# inktime_schematic.net
KiCad netlist of a schematic drawn in EAGLE
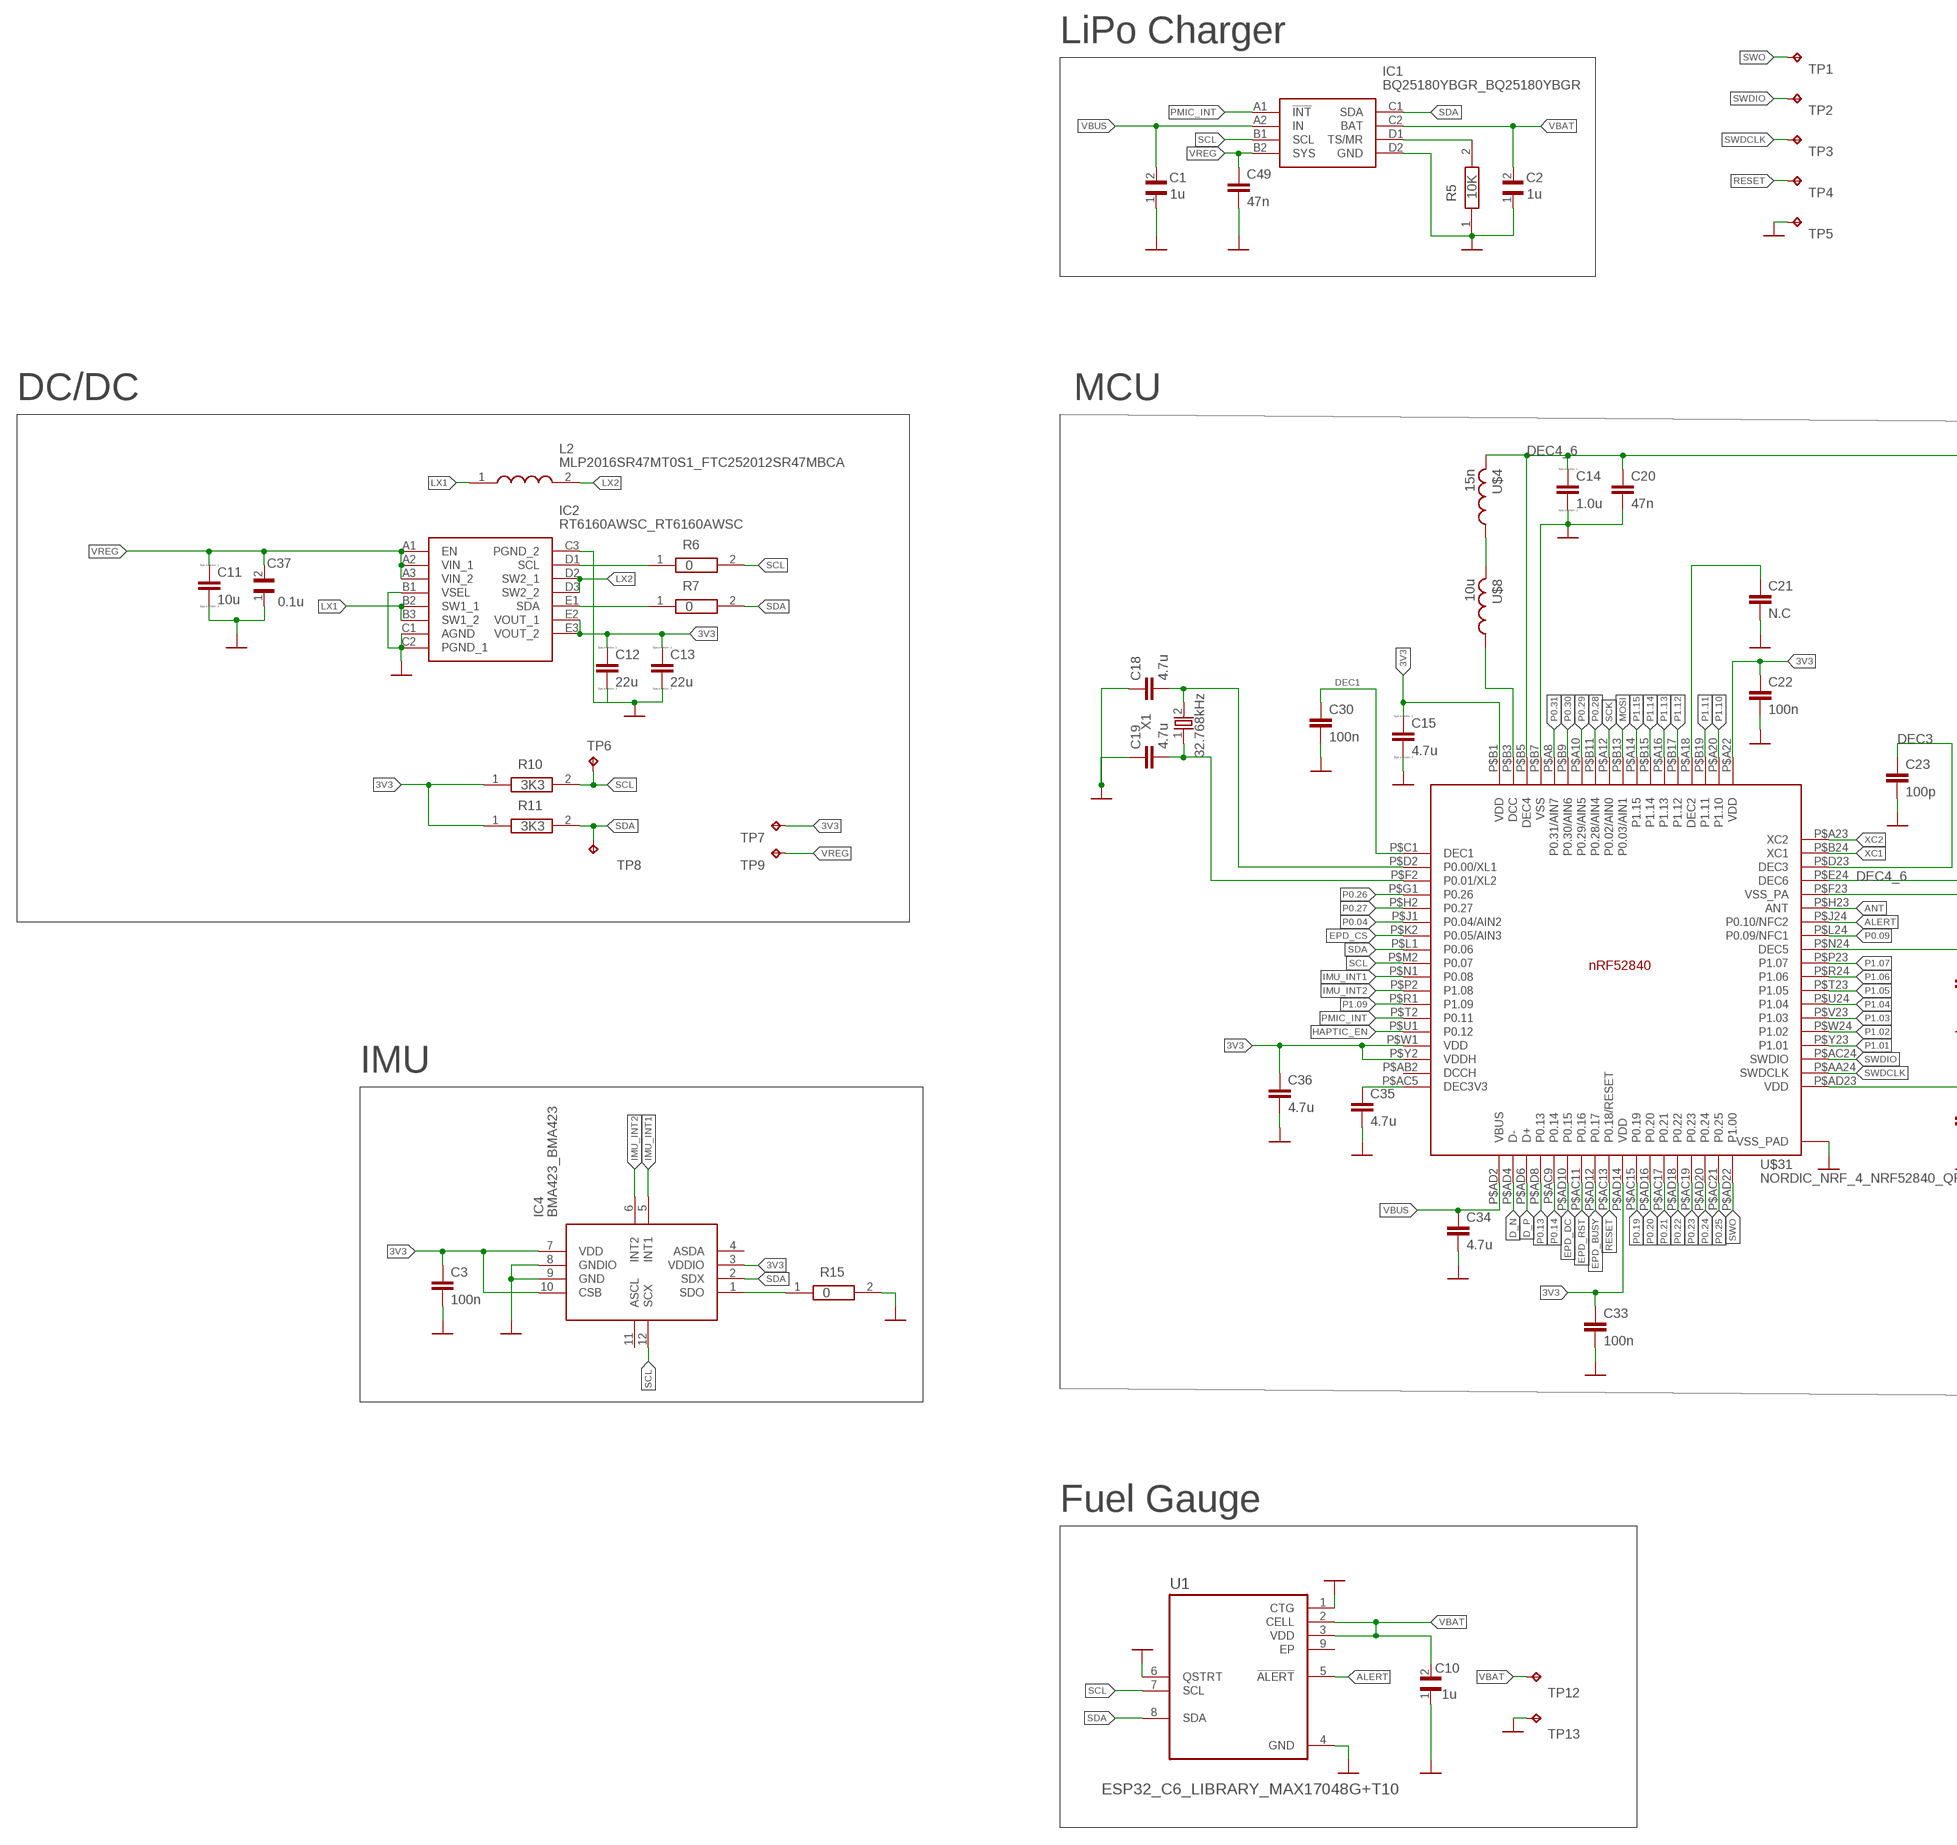
[diagram p0: schematic, sheet 1, part 1 of 2]
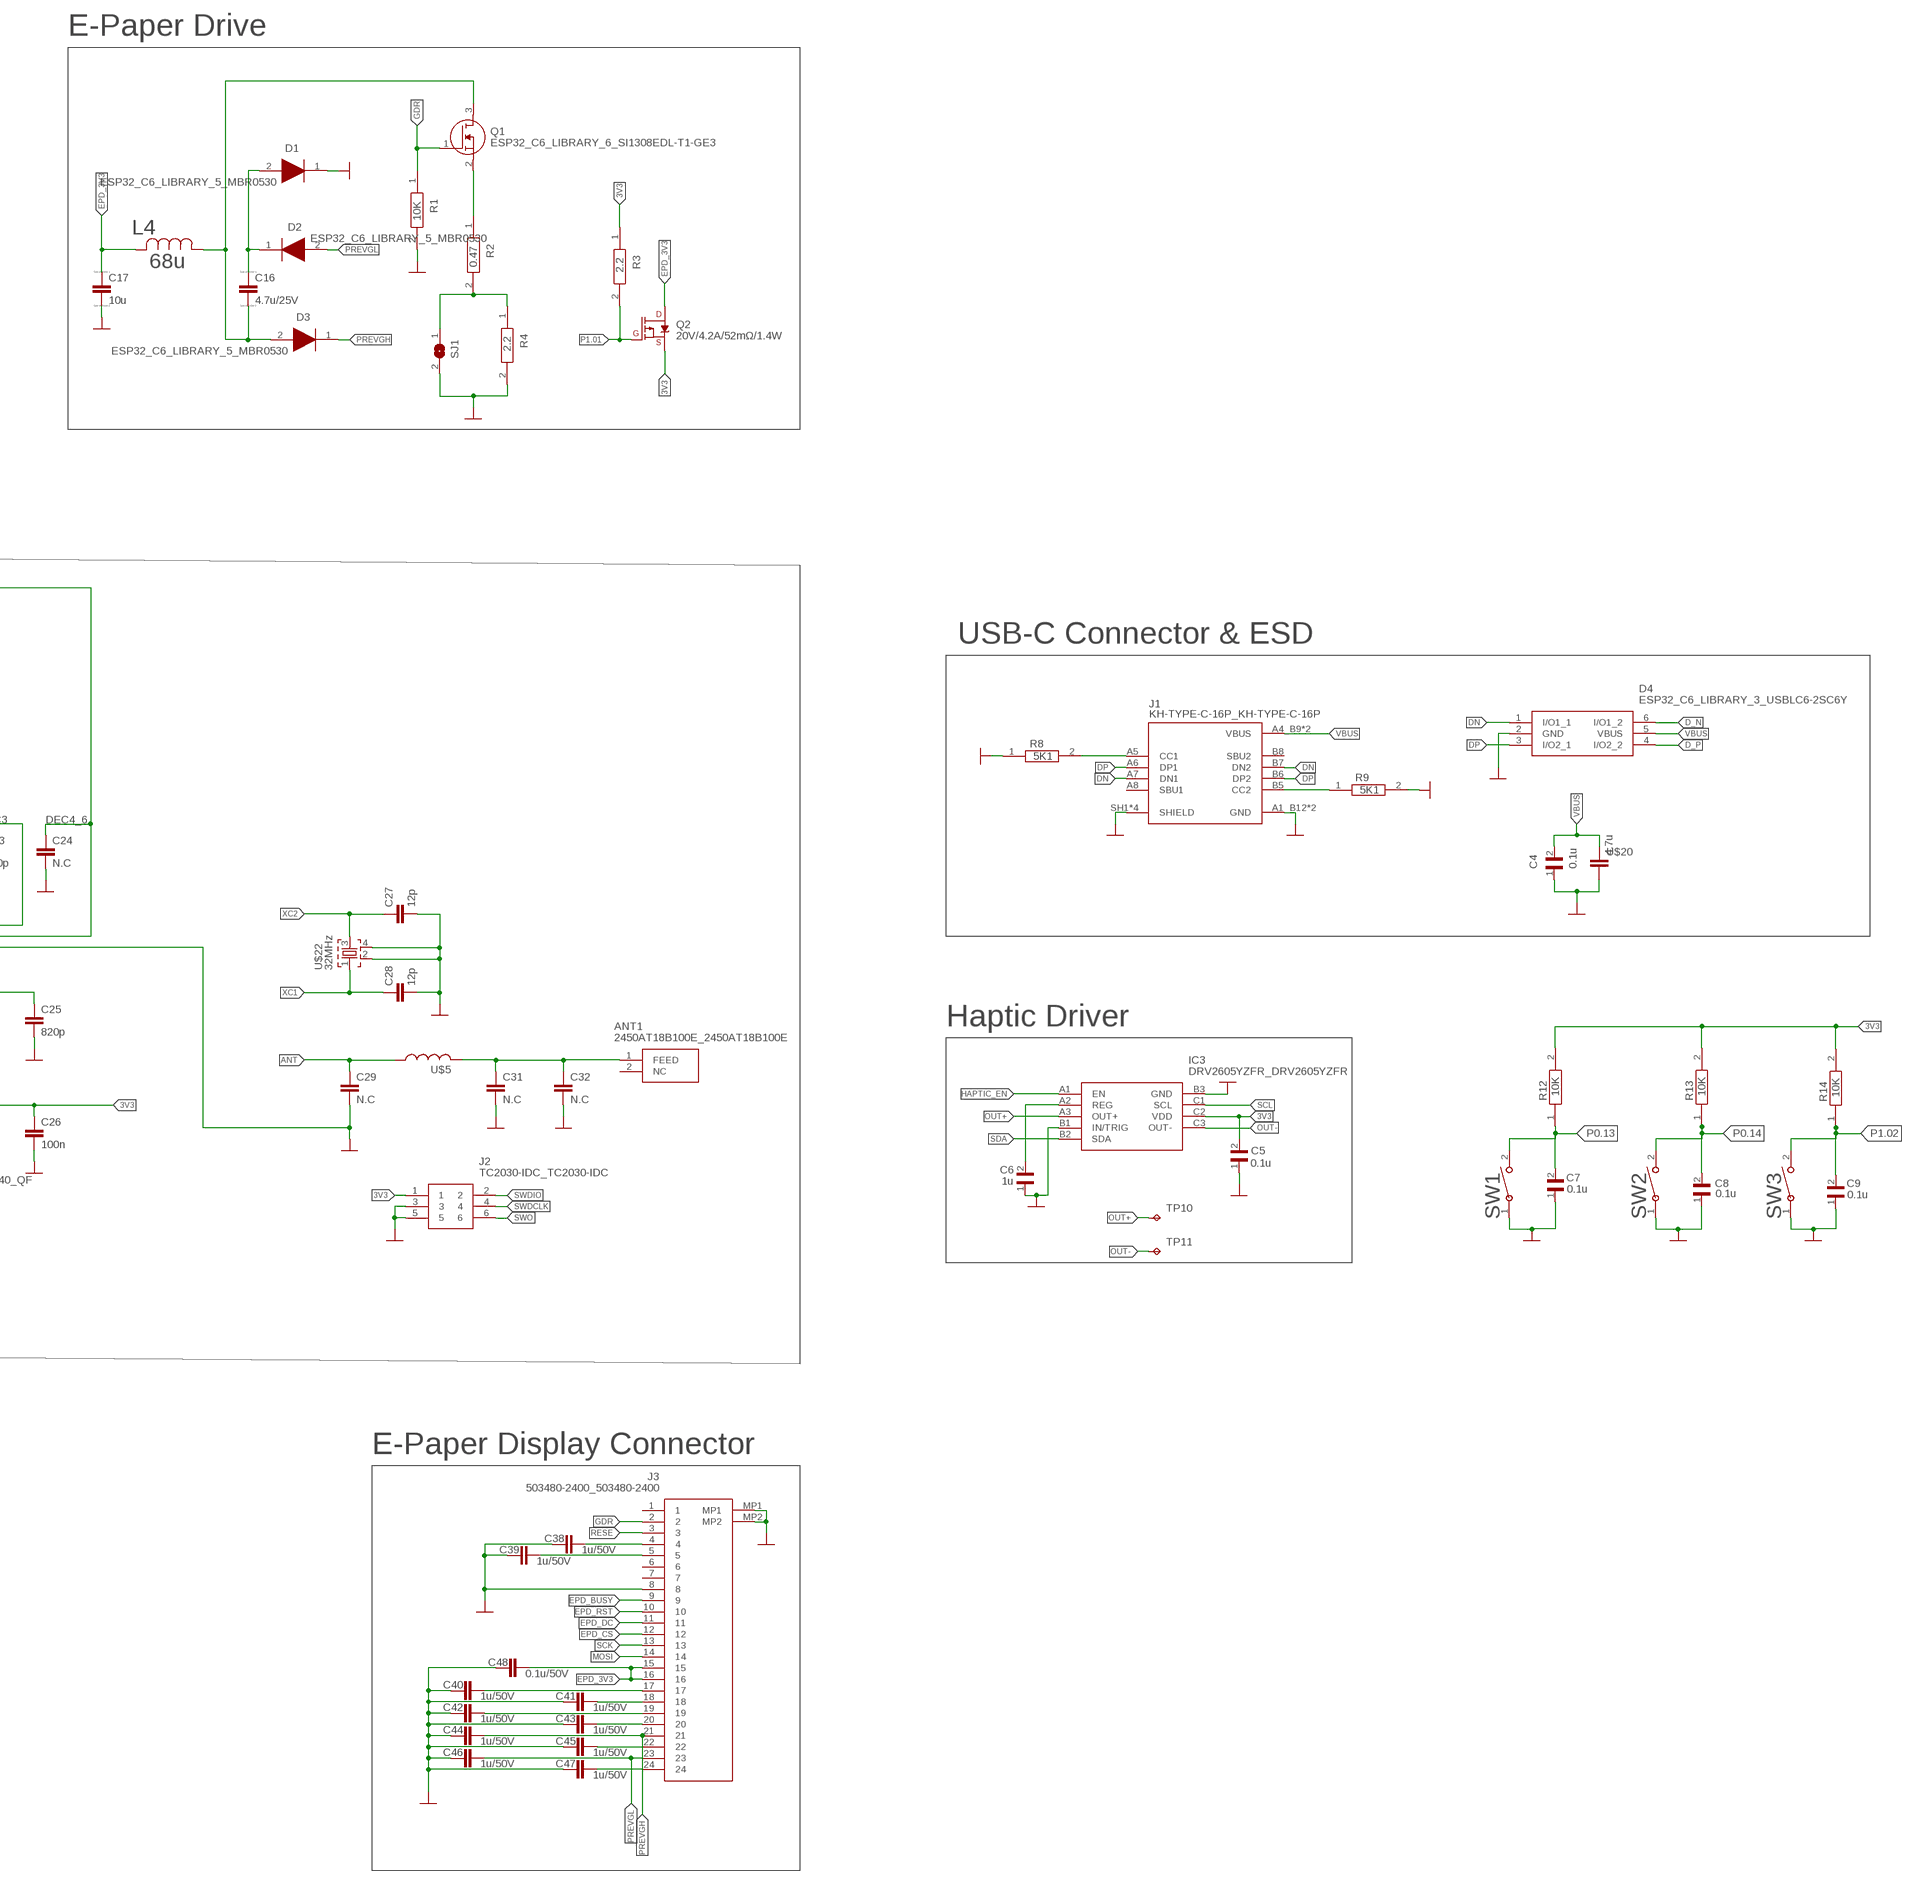
[diagram p1: schematic, sheet 1, part 2 of 2]

(export (version "E")
  (design (tool "Eeschema 10.0.6"))
  (components
    (comp (ref "ANT1")
      (value "2450AT18B100E_2450AT18B100E")
      (footprint "eagle-import:2450AT18B100E_ANTC3216X140N")
      (fields
        (field (name "ARROW_PART_NUMBER") "2450AT18B100E")
        (field (name "MOUSER_PART_NUMBER") "609-2450AT18B100E")
      )
      (libsource (lib "eagle-import") (part "2450AT18B100E_2450AT18B100E"))
    )
    (comp (ref "C1")
      (value "1u")
      (footprint "eagle-import:GRM011R60J152KE01L_2_CAPC0201X13N")
      (fields (field (name "MF") "Murata") (field (name "MP") "GRM011R60J152KE01L"))
      (libsource (lib "eagle-import") (part "GRM011R60J152KE01L_2_GRM011R60J152KE01L"))
    )
    (comp (ref "C2")
      (value "1u")
      (footprint "eagle-import:GRM011R60J152KE01L_2_CAPC0201X13N")
      (fields (field (name "MF") "Murata") (field (name "MP") "GRM011R60J152KE01L"))
      (libsource (lib "eagle-import") (part "GRM011R60J152KE01L_2_GRM011R60J152KE01L"))
    )
    (comp (ref "C3")
      (value "100n")
      (footprint "eagle-import:NORDIC_NRF_3_RESC0201_L")
      (libsource (lib "eagle-import") (part "NORDIC_NRF_3_CAPACITOR_0201_L"))
    )
    (comp (ref "C4")
      (value "0.1u")
      (footprint "eagle-import:GRM011R60J152KE01L_2_CAPC0201X13N")
      (fields (field (name "MF") "Murata") (field (name "MP") "GRM011R60J152KE01L"))
      (libsource (lib "eagle-import") (part "GRM011R60J152KE01L_2_GRM011R60J152KE01L"))
    )
    (comp (ref "C5")
      (value "0.1u")
      (footprint "eagle-import:GRM011R60J152KE01L_2_CAPC0201X13N")
      (fields (field (name "MF") "Murata") (field (name "MP") "GRM011R60J152KE01L"))
      (libsource (lib "eagle-import") (part "GRM011R60J152KE01L_2_GRM011R60J152KE01L"))
    )
    (comp (ref "C6")
      (value "1u")
      (footprint "eagle-import:GRM011R60J152KE01L_2_CAPC0201X13N")
      (fields (field (name "MF") "Murata") (field (name "MP") "GRM011R60J152KE01L"))
      (libsource (lib "eagle-import") (part "GRM011R60J152KE01L_2_GRM011R60J152KE01L"))
    )
    (comp (ref "C7")
      (value "0.1u")
      (footprint "eagle-import:GRM011R60J152KE01L_2_CAPC0201X13N")
      (fields (field (name "MF") "Murata") (field (name "MP") "GRM011R60J152KE01L"))
      (libsource (lib "eagle-import") (part "GRM011R60J152KE01L_2_GRM011R60J152KE01L"))
    )
    (comp (ref "C8")
      (value "0.1u")
      (footprint "eagle-import:GRM011R60J152KE01L_2_CAPC0201X13N")
      (fields (field (name "MF") "Murata") (field (name "MP") "GRM011R60J152KE01L"))
      (libsource (lib "eagle-import") (part "GRM011R60J152KE01L_2_GRM011R60J152KE01L"))
    )
    (comp (ref "C9")
      (value "0.1u")
      (footprint "eagle-import:GRM011R60J152KE01L_2_CAPC0201X13N")
      (fields (field (name "MF") "Murata") (field (name "MP") "GRM011R60J152KE01L"))
      (libsource (lib "eagle-import") (part "GRM011R60J152KE01L_2_GRM011R60J152KE01L"))
    )
    (comp (ref "C10")
      (value "1u")
      (footprint "eagle-import:GRM011R60J152KE01L_2_CAPC0201X13N")
      (fields (field (name "MF") "Murata") (field (name "MP") "GRM011R60J152KE01L"))
      (libsource (lib "eagle-import") (part "GRM011R60J152KE01L_2_GRM011R60J152KE01L"))
    )
    (comp (ref "C11")
      (value "10u")
      (footprint "eagle-import:ESP32_C6_LIBRARY_1_ESP32_WROVER_EAGLE-LTSPICE_C0402")
      (libsource (lib "eagle-import") (part "ESP32_C6_LIBRARY_1_ESP32_WROVER_EAGLE-LTSPICE_CC0402"))
    )
    (comp (ref "C12")
      (value "22u")
      (footprint "eagle-import:ESP32_C6_LIBRARY_1_ESP32_WROVER_EAGLE-LTSPICE_C0402")
      (libsource (lib "eagle-import") (part "ESP32_C6_LIBRARY_1_ESP32_WROVER_EAGLE-LTSPICE_CC0402"))
    )
    (comp (ref "C13")
      (value "22u")
      (footprint "eagle-import:ESP32_C6_LIBRARY_1_ESP32_WROVER_EAGLE-LTSPICE_C0402")
      (libsource (lib "eagle-import") (part "ESP32_C6_LIBRARY_1_ESP32_WROVER_EAGLE-LTSPICE_CC0402"))
    )
    (comp (ref "C14")
      (value "1.0u")
      (footprint "eagle-import:ESP32_C6_LIBRARY_1_ESP32_WROVER_EAGLE-LTSPICE_C0402")
      (libsource (lib "eagle-import") (part "ESP32_C6_LIBRARY_1_ESP32_WROVER_EAGLE-LTSPICE_CC0402"))
    )
    (comp (ref "C15")
      (value "4.7u")
      (footprint "eagle-import:ESP32_C6_LIBRARY_1_ESP32_WROVER_EAGLE-LTSPICE_C0402")
      (libsource (lib "eagle-import") (part "ESP32_C6_LIBRARY_1_ESP32_WROVER_EAGLE-LTSPICE_CC0402"))
    )
    (comp (ref "C16")
      (value "4.7u/25V")
      (footprint "eagle-import:ESP32_C6_LIBRARY_1_ESP32_WROVER_EAGLE-LTSPICE_C0402")
      (libsource (lib "eagle-import") (part "ESP32_C6_LIBRARY_1_ESP32_WROVER_EAGLE-LTSPICE_CC0402"))
    )
    (comp (ref "C17")
      (value "10u")
      (footprint "eagle-import:ESP32_C6_LIBRARY_1_ESP32_WROVER_EAGLE-LTSPICE_C0402")
      (libsource (lib "eagle-import") (part "ESP32_C6_LIBRARY_1_ESP32_WROVER_EAGLE-LTSPICE_CC0402"))
    )
    (comp (ref "C18")
      (value "4.7u")
      (footprint "eagle-import:NORDIC_NRF_3_RESC0201_L")
      (libsource (lib "eagle-import") (part "NORDIC_NRF_3_CAPACITOR_0201_L"))
    )
    (comp (ref "C19")
      (value "4.7u")
      (footprint "eagle-import:NORDIC_NRF_3_RESC0201_L")
      (libsource (lib "eagle-import") (part "NORDIC_NRF_3_CAPACITOR_0201_L"))
    )
    (comp (ref "C20")
      (value "47n")
      (footprint "eagle-import:NORDIC_NRF_3_RESC0201_L")
      (libsource (lib "eagle-import") (part "NORDIC_NRF_3_CAPACITOR_0201_L"))
    )
    (comp (ref "C21")
      (value "N.C")
      (footprint "eagle-import:NORDIC_NRF_3_RESC0201_L")
      (libsource (lib "eagle-import") (part "NORDIC_NRF_3_CAPACITOR_0201_L"))
    )
    (comp (ref "C22")
      (value "100n")
      (footprint "eagle-import:NORDIC_NRF_3_RESC0201_L")
      (libsource (lib "eagle-import") (part "NORDIC_NRF_3_CAPACITOR_0201_L"))
    )
    (comp (ref "C23")
      (value "100p")
      (footprint "eagle-import:NORDIC_NRF_3_RESC0201_L")
      (libsource (lib "eagle-import") (part "NORDIC_NRF_3_CAPACITOR_0201_L"))
    )
    (comp (ref "C24")
      (value "N.C")
      (footprint "eagle-import:NORDIC_NRF_3_RESC0201_L")
      (libsource (lib "eagle-import") (part "NORDIC_NRF_3_CAPACITOR_0201_L"))
    )
    (comp (ref "C25")
      (value "820p")
      (footprint "eagle-import:NORDIC_NRF_3_RESC0201_L")
      (libsource (lib "eagle-import") (part "NORDIC_NRF_3_CAPACITOR_0201_L"))
    )
    (comp (ref "C26")
      (value "100n")
      (footprint "eagle-import:NORDIC_NRF_3_RESC0201_L")
      (libsource (lib "eagle-import") (part "NORDIC_NRF_3_CAPACITOR_0201_L"))
    )
    (comp (ref "C27")
      (value "12p")
      (footprint "eagle-import:NORDIC_NRF_3_RESC0201_L")
      (libsource (lib "eagle-import") (part "NORDIC_NRF_3_CAPACITOR_0201_L"))
    )
    (comp (ref "C28")
      (value "12p")
      (footprint "eagle-import:NORDIC_NRF_3_RESC0201_L")
      (libsource (lib "eagle-import") (part "NORDIC_NRF_3_CAPACITOR_0201_L"))
    )
    (comp (ref "C29")
      (value "N.C")
      (footprint "eagle-import:NORDIC_NRF_3_RESC0201_L")
      (libsource (lib "eagle-import") (part "NORDIC_NRF_3_CAPACITOR_0201_L"))
    )
    (comp (ref "C30")
      (value "100n")
      (footprint "eagle-import:NORDIC_NRF_3_RESC0201_L")
      (libsource (lib "eagle-import") (part "NORDIC_NRF_3_CAPACITOR_0201_L"))
    )
    (comp (ref "C31")
      (value "N.C")
      (footprint "eagle-import:NORDIC_NRF_3_RESC0201_L")
      (libsource (lib "eagle-import") (part "NORDIC_NRF_3_CAPACITOR_0201_L"))
    )
    (comp (ref "C32")
      (value "N.C")
      (footprint "eagle-import:NORDIC_NRF_3_RESC0201_L")
      (libsource (lib "eagle-import") (part "NORDIC_NRF_3_CAPACITOR_0201_L"))
    )
    (comp (ref "C33")
      (value "100n")
      (footprint "eagle-import:NORDIC_NRF_3_RESC0201_L")
      (libsource (lib "eagle-import") (part "NORDIC_NRF_3_CAPACITOR_0201_L"))
    )
    (comp (ref "C34")
      (value "4.7u")
      (footprint "eagle-import:NORDIC_NRF_3_RESC0201_L")
      (libsource (lib "eagle-import") (part "NORDIC_NRF_3_CAPACITOR_0201_L"))
    )
    (comp (ref "C35")
      (value "4.7u")
      (footprint "eagle-import:NORDIC_NRF_3_RESC0201_L")
      (libsource (lib "eagle-import") (part "NORDIC_NRF_3_CAPACITOR_0201_L"))
    )
    (comp (ref "C36")
      (value "4.7u")
      (footprint "eagle-import:NORDIC_NRF_3_RESC0201_L")
      (libsource (lib "eagle-import") (part "NORDIC_NRF_3_CAPACITOR_0201_L"))
    )
    (comp (ref "C37")
      (value "0.1u")
      (footprint "eagle-import:GRM011R60J152KE01L_2_CAPC0201X13N")
      (fields (field (name "MF") "Murata") (field (name "MP") "GRM011R60J152KE01L"))
      (libsource (lib "eagle-import") (part "GRM011R60J152KE01L_2_GRM011R60J152KE01L"))
    )
    (comp (ref "C38")
      (value "1u/50V")
      (footprint "eagle-import:NORDIC_NRF_3_RESC0201_L")
      (libsource (lib "eagle-import") (part "NORDIC_NRF_3_CAPACITOR_0201_L"))
    )
    (comp (ref "C39")
      (value "1u/50V")
      (footprint "eagle-import:NORDIC_NRF_3_RESC0201_L")
      (libsource (lib "eagle-import") (part "NORDIC_NRF_3_CAPACITOR_0201_L"))
    )
    (comp (ref "C40")
      (value "1u/50V")
      (footprint "eagle-import:NORDIC_NRF_3_RESC0201_L")
      (libsource (lib "eagle-import") (part "NORDIC_NRF_3_CAPACITOR_0201_L"))
    )
    (comp (ref "C41")
      (value "1u/50V")
      (footprint "eagle-import:NORDIC_NRF_3_RESC0201_L")
      (libsource (lib "eagle-import") (part "NORDIC_NRF_3_CAPACITOR_0201_L"))
    )
    (comp (ref "C42")
      (value "1u/50V")
      (footprint "eagle-import:NORDIC_NRF_3_RESC0201_L")
      (libsource (lib "eagle-import") (part "NORDIC_NRF_3_CAPACITOR_0201_L"))
    )
    (comp (ref "C43")
      (value "1u/50V")
      (footprint "eagle-import:NORDIC_NRF_3_RESC0201_L")
      (libsource (lib "eagle-import") (part "NORDIC_NRF_3_CAPACITOR_0201_L"))
    )
    (comp (ref "C44")
      (value "1u/50V")
      (footprint "eagle-import:NORDIC_NRF_3_RESC0201_L")
      (libsource (lib "eagle-import") (part "NORDIC_NRF_3_CAPACITOR_0201_L"))
    )
    (comp (ref "C45")
      (value "1u/50V")
      (footprint "eagle-import:NORDIC_NRF_3_RESC0201_L")
      (libsource (lib "eagle-import") (part "NORDIC_NRF_3_CAPACITOR_0201_L"))
    )
    (comp (ref "C46")
      (value "1u/50V")
      (footprint "eagle-import:NORDIC_NRF_3_RESC0201_L")
      (libsource (lib "eagle-import") (part "NORDIC_NRF_3_CAPACITOR_0201_L"))
    )
    (comp (ref "C47")
      (value "1u/50V")
      (footprint "eagle-import:NORDIC_NRF_3_RESC0201_L")
      (libsource (lib "eagle-import") (part "NORDIC_NRF_3_CAPACITOR_0201_L"))
    )
    (comp (ref "C48")
      (value "0.1u/50V")
      (footprint "eagle-import:NORDIC_NRF_3_RESC0201_L")
      (libsource (lib "eagle-import") (part "NORDIC_NRF_3_CAPACITOR_0201_L"))
    )
    (comp (ref "C49")
      (value "47n")
      (footprint "eagle-import:NORDIC_NRF_3_RESC0201_L")
      (libsource (lib "eagle-import") (part "NORDIC_NRF_3_CAPACITOR_0201_L"))
    )
    (comp (ref "D1")
      (value "ESP32_C6_LIBRARY_5_MBR0530")
      (footprint "eagle-import:ESP32_C6_LIBRARY_5_SOD3716X135N")
      (fields (field (name "MF") "ON Semiconductor") (field (name "MP") "MBR0530"))
      (libsource (lib "eagle-import") (part "ESP32_C6_LIBRARY_5_MBR0530"))
    )
    (comp (ref "D2")
      (value "ESP32_C6_LIBRARY_5_MBR0530")
      (footprint "eagle-import:ESP32_C6_LIBRARY_5_SOD3716X135N")
      (fields (field (name "MF") "ON Semiconductor") (field (name "MP") "MBR0530"))
      (libsource (lib "eagle-import") (part "ESP32_C6_LIBRARY_5_MBR0530"))
    )
    (comp (ref "D3")
      (value "ESP32_C6_LIBRARY_5_MBR0530")
      (footprint "eagle-import:ESP32_C6_LIBRARY_5_SOD3716X135N")
      (fields (field (name "MF") "ON Semiconductor") (field (name "MP") "MBR0530"))
      (libsource (lib "eagle-import") (part "ESP32_C6_LIBRARY_5_MBR0530"))
    )
    (comp (ref "D4")
      (value "ESP32_C6_LIBRARY_3_USBLC6-2SC6Y")
      (footprint "eagle-import:ESP32_C6_LIBRARY_3_SOT95P280X145-6N")
      (fields (field (name "MF") "STMicroelectronics") (field (name "MP") "USBLC6-2SC6Y"))
      (libsource (lib "eagle-import") (part "ESP32_C6_LIBRARY_3_USBLC6-2SC6Y"))
    )
    (comp (ref "IC1")
      (value "BQ25180YBGR_BQ25180YBGR")
      (footprint "eagle-import:BQ25180YBGR_BGA8C40P2X4_100X155X50")
      (fields
        (field (name "ARROW_PART_NUMBER") "BQ25180YBGR")
        (field (name "MOUSER_PART_NUMBER") "595-BQ25180YBGR")
      )
      (libsource (lib "eagle-import") (part "BQ25180YBGR_BQ25180YBGR"))
    )
    (comp (ref "IC2")
      (value "RT6160AWSC_RT6160AWSC")
      (footprint "eagle-import:RT6160AWSC_BGA15C40P3X5_140X230X60")
      (fields
        (field (name "MANUFACTURER_PART_NUMBER") "RT6160AWSC")
        (field (name "MOUSER_PART_NUMBER") "835-RT6160AWSC")
      )
      (libsource (lib "eagle-import") (part "RT6160AWSC_RT6160AWSC"))
    )
    (comp (ref "IC3")
      (value "DRV2605YZFR_DRV2605YZFR")
      (footprint "eagle-import:DRV2605YZFR_BGA9C50P3X3_144X144X62")
      (fields (field (name "ARROW_PART_NUMBER") "DRV2605YZFR"))
      (libsource (lib "eagle-import") (part "DRV2605YZFR_DRV2605YZFR"))
    )
    (comp (ref "IC4")
      (value "BMA423_BMA423")
      (footprint "eagle-import:BMA423_BMA423")
      (fields (field (name "ARROW_PART_NUMBER") "BMA423") (field (name "MOUSER_PART_NUMBER") "262-BMA423"))
      (libsource (lib "eagle-import") (part "BMA423_BMA423"))
    )
    (comp (ref "J1")
      (value "KH-TYPE-C-16P_KH-TYPE-C-16P")
      (footprint "eagle-import:KH-TYPE-C-16P_KINGHELM_KH-TYPE-C-16P")
      (fields (field (name "MF") "kinghelm") (field (name "MP") "KH-TYPE-C-16P"))
      (libsource (lib "eagle-import") (part "KH-TYPE-C-16P_KH-TYPE-C-16P"))
    )
    (comp (ref "J2")
      (value "TC2030-IDC_TC2030-IDC")
      (footprint "eagle-import:TC2030-IDC_TC2030IDC")
      (fields (field (name "MANUFACTURER_PART_NUMBER") "TC2030-IDC"))
      (libsource (lib "eagle-import") (part "TC2030-IDC_TC2030-IDC"))
    )
    (comp (ref "J3")
      (value "503480-2400_503480-2400")
      (footprint "eagle-import:503480-2400_5034802400")
      (fields
        (field (name "MANUFACTURER_PART_NUMBER") "503480-2400")
        (field (name "MOUSER_PART_NUMBER") "538-503480-2400")
      )
      (libsource (lib "eagle-import") (part "503480-2400_503480-2400"))
    )
    (comp (ref "L2")
      (value "MLP2016SR47MT0S1_FTC252012SR47MBCA")
      (footprint "eagle-import:MLP2016SR47MT0S1_INDC2016X100N")
      (fields (field (name "MANUFACTURER_PART_NUMBER") "FTC252012SR47MBCA"))
      (libsource (lib "eagle-import") (part "MLP2016SR47MT0S1_FTC252012SR47MBCA"))
    )
    (comp (ref "L4")
      (value "68u")
      (footprint "eagle-import:ESP32_C6_LIBRARY_2_IND_4828-WE-TPC_WRE")
      (fields
        (field (name "MANUFACTURER_PART_NUMBER") "744043680")
        (field (name "COPYRIGHT") "Copyright (C) 2024 Ultra Librarian. All rights reserved.")
      )
      (libsource (lib "eagle-import") (part "ESP32_C6_LIBRARY_2_744043680IND_4828-WE-TPC_WRE"))
    )
    (comp (ref "Q1")
      (value "ESP32_C6_LIBRARY_6_SI1308EDL-T1-GE3")
      (footprint "eagle-import:ESP32_C6_LIBRARY_6_SOT65P210X110-3N")
      (fields (field (name "MF") "Vishay Siliconix") (field (name "MP") "SI1308EDL-T1-GE3"))
      (libsource (lib "eagle-import") (part "ESP32_C6_LIBRARY_6_SI1308EDL-T1-GE3"))
    )
    (comp (ref "Q2")
      (value "20V/4.2A/52mΩ/1.4W")
      (footprint "eagle-import:ESP32_C6_LIBRARY_4_ESP32_C6_LIBRARY_4_ESP32_C6_LIBRARY_4_ESP32_C6_LIBRARY_4_ESP32_WROVER_SPARKFUN-DISCRETESEMI_SOT23-3")
      (libsource (lib "eagle-import") (part "ESP32_C6_LIBRARY_4_ESP32_WROVER_SPARKFUN-DISCRETESEMI_MOSFET_PCH-DMG2305UX-7"))
    )
    (comp (ref "R1")
      (value "10K")
      (footprint "eagle-import:ERA-1AEB3401C_0201")
      (libsource (lib "eagle-import") (part "ERA-1AEB3401C_CPF0201D7K68C1"))
    )
    (comp (ref "R2")
      (value "0.47")
      (footprint "eagle-import:ERA-1AEB3401C_0201")
      (libsource (lib "eagle-import") (part "ERA-1AEB3401C_CPF0201D7K68C1"))
    )
    (comp (ref "R3")
      (value "2.2")
      (footprint "eagle-import:ERA-1AEB3401C_0201")
      (libsource (lib "eagle-import") (part "ERA-1AEB3401C_CPF0201D7K68C1"))
    )
    (comp (ref "R4")
      (value "2.2")
      (footprint "eagle-import:ERA-1AEB3401C_0201")
      (libsource (lib "eagle-import") (part "ERA-1AEB3401C_CPF0201D7K68C1"))
    )
    (comp (ref "R5")
      (value "10K")
      (footprint "eagle-import:ERA-1AEB3401C_0201")
      (libsource (lib "eagle-import") (part "ERA-1AEB3401C_CPF0201D7K68C1"))
    )
    (comp (ref "R6")
      (value "0")
      (footprint "eagle-import:ERA-1AEB3401C_0201")
      (libsource (lib "eagle-import") (part "ERA-1AEB3401C_CPF0201D7K68C1"))
    )
    (comp (ref "R7")
      (value "0")
      (footprint "eagle-import:ERA-1AEB3401C_0201")
      (libsource (lib "eagle-import") (part "ERA-1AEB3401C_CPF0201D7K68C1"))
    )
    (comp (ref "R8")
      (value "5K1")
      (footprint "eagle-import:ERA-1AEB3401C_0201")
      (libsource (lib "eagle-import") (part "ERA-1AEB3401C_CPF0201D7K68C1"))
    )
    (comp (ref "R9")
      (value "5K1")
      (footprint "eagle-import:ERA-1AEB3401C_0201")
      (libsource (lib "eagle-import") (part "ERA-1AEB3401C_CPF0201D7K68C1"))
    )
    (comp (ref "R10")
      (value "3K3")
      (footprint "eagle-import:ERA-1AEB3401C_0201")
      (libsource (lib "eagle-import") (part "ERA-1AEB3401C_CPF0201D7K68C1"))
    )
    (comp (ref "R11")
      (value "3K3")
      (footprint "eagle-import:ERA-1AEB3401C_0201")
      (libsource (lib "eagle-import") (part "ERA-1AEB3401C_CPF0201D7K68C1"))
    )
    (comp (ref "R12")
      (value "10K")
      (footprint "eagle-import:ERA-1AEB3401C_0201")
      (libsource (lib "eagle-import") (part "ERA-1AEB3401C_CPF0201D7K68C1"))
    )
    (comp (ref "R13")
      (value "10K")
      (footprint "eagle-import:ERA-1AEB3401C_0201")
      (libsource (lib "eagle-import") (part "ERA-1AEB3401C_CPF0201D7K68C1"))
    )
    (comp (ref "R14")
      (value "10K")
      (footprint "eagle-import:ERA-1AEB3401C_0201")
      (libsource (lib "eagle-import") (part "ERA-1AEB3401C_CPF0201D7K68C1"))
    )
    (comp (ref "R15")
      (value "0")
      (footprint "eagle-import:ERA-1AEB3401C_0201")
      (libsource (lib "eagle-import") (part "ERA-1AEB3401C_CPF0201D7K68C1"))
    )
    (comp (ref "SJ1")
      (value "ESP32_C6_LIBRARY_7_JUMPER_SJ")
      (footprint "eagle-import:ESP32_C6_LIBRARY_7_JUMPER_SJ")
      (libsource (lib "eagle-import") (part "ESP32_C6_LIBRARY_7_JUMPER_SJ"))
    )
    (comp (ref "SW1")
      (value "2025-10-22_07-23-44_LIBRARY_EVP-AKE31ASW_EVP-AKE31A_PAN")
      (footprint "eagle-import:2025-10-22_07-23-44_LIBRARY_SW_EVP-AKE31A_PAN")
      (fields
        (field (name "MANUFACTURER_PART_NUMBER") "EVP-AKE31A")
        (field (name "COPYRIGHT") "Copyright (C) 2025 Ultra Librarian. All rights reserved.")
      )
      (libsource (lib "eagle-import") (part "2025-10-22_07-23-44_LIBRARY_EVP-AKE31ASW_EVP-AKE31A_PAN"))
    )
    (comp (ref "SW2")
      (value "2025-10-22_07-23-44_LIBRARY_EVP-AKE31ASW_EVP-AKE31A_PAN")
      (footprint "eagle-import:2025-10-22_07-23-44_LIBRARY_SW_EVP-AKE31A_PAN")
      (fields
        (field (name "MANUFACTURER_PART_NUMBER") "EVP-AKE31A")
        (field (name "COPYRIGHT") "Copyright (C) 2025 Ultra Librarian. All rights reserved.")
      )
      (libsource (lib "eagle-import") (part "2025-10-22_07-23-44_LIBRARY_EVP-AKE31ASW_EVP-AKE31A_PAN"))
    )
    (comp (ref "SW3")
      (value "2025-10-22_07-23-44_LIBRARY_EVP-AKE31ASW_EVP-AKE31A_PAN")
      (footprint "eagle-import:2025-10-22_07-23-44_LIBRARY_SW_EVP-AKE31A_PAN")
      (fields
        (field (name "MANUFACTURER_PART_NUMBER") "EVP-AKE31A")
        (field (name "COPYRIGHT") "Copyright (C) 2025 Ultra Librarian. All rights reserved.")
      )
      (libsource (lib "eagle-import") (part "2025-10-22_07-23-44_LIBRARY_EVP-AKE31ASW_EVP-AKE31A_PAN"))
    )
    (comp (ref "TP1")
      (value "HECTOR_WATCH_1_TPTP20R")
      (footprint "eagle-import:HECTOR_WATCH_1_TP20R")
      (libsource (lib "eagle-import") (part "HECTOR_WATCH_1_TPTP20R"))
    )
    (comp (ref "TP2")
      (value "HECTOR_WATCH_1_TPTP20R")
      (footprint "eagle-import:HECTOR_WATCH_1_TP20R")
      (libsource (lib "eagle-import") (part "HECTOR_WATCH_1_TPTP20R"))
    )
    (comp (ref "TP3")
      (value "HECTOR_WATCH_1_TPTP20R")
      (footprint "eagle-import:HECTOR_WATCH_1_TP20R")
      (libsource (lib "eagle-import") (part "HECTOR_WATCH_1_TPTP20R"))
    )
    (comp (ref "TP4")
      (value "HECTOR_WATCH_1_TPTP20R")
      (footprint "eagle-import:HECTOR_WATCH_1_TP20R")
      (libsource (lib "eagle-import") (part "HECTOR_WATCH_1_TPTP20R"))
    )
    (comp (ref "TP5")
      (value "HECTOR_WATCH_1_TPTP20R")
      (footprint "eagle-import:HECTOR_WATCH_1_TP20R")
      (libsource (lib "eagle-import") (part "HECTOR_WATCH_1_TPTP20R"))
    )
    (comp (ref "TP6")
      (value "HECTOR_WATCH_1_TPTP20R")
      (footprint "eagle-import:HECTOR_WATCH_1_TP20R")
      (libsource (lib "eagle-import") (part "HECTOR_WATCH_1_TPTP20R"))
    )
    (comp (ref "TP7")
      (value "HECTOR_WATCH_1_TPTP20R")
      (footprint "eagle-import:HECTOR_WATCH_1_TP20R")
      (libsource (lib "eagle-import") (part "HECTOR_WATCH_1_TPTP20R"))
    )
    (comp (ref "TP8")
      (value "HECTOR_WATCH_1_TPTP20R")
      (footprint "eagle-import:HECTOR_WATCH_1_TP20R")
      (libsource (lib "eagle-import") (part "HECTOR_WATCH_1_TPTP20R"))
    )
    (comp (ref "TP9")
      (value "HECTOR_WATCH_1_TPTP20R")
      (footprint "eagle-import:HECTOR_WATCH_1_TP20R")
      (libsource (lib "eagle-import") (part "HECTOR_WATCH_1_TPTP20R"))
    )
    (comp (ref "TP10")
      (value "HECTOR_WATCH_1_TPTP20R")
      (footprint "eagle-import:HECTOR_WATCH_1_TP20R")
      (libsource (lib "eagle-import") (part "HECTOR_WATCH_1_TPTP20R"))
    )
    (comp (ref "TP11")
      (value "HECTOR_WATCH_1_TPTP20R")
      (footprint "eagle-import:HECTOR_WATCH_1_TP20R")
      (libsource (lib "eagle-import") (part "HECTOR_WATCH_1_TPTP20R"))
    )
    (comp (ref "TP12")
      (value "HECTOR_WATCH_1_TPTP20R")
      (footprint "eagle-import:HECTOR_WATCH_1_TP20R")
      (libsource (lib "eagle-import") (part "HECTOR_WATCH_1_TPTP20R"))
    )
    (comp (ref "TP13")
      (value "HECTOR_WATCH_1_TPTP20R")
      (footprint "eagle-import:HECTOR_WATCH_1_TP20R")
      (libsource (lib "eagle-import") (part "HECTOR_WATCH_1_TPTP20R"))
    )
    (comp (ref "U$4")
      (value "15n")
      (footprint "eagle-import:NORDIC_NRF_2_RESC0402_L")
      (libsource (lib "eagle-import") (part "NORDIC_NRF_2_INDUCTOR_0402_L"))
    )
    (comp (ref "U$5")
      (value "NORDIC_NRF_2_INDUCTOR_0402_L")
      (footprint "eagle-import:NORDIC_NRF_2_RESC0402_L")
      (libsource (lib "eagle-import") (part "NORDIC_NRF_2_INDUCTOR_0402_L"))
    )
    (comp (ref "U$8")
      (value "10u")
      (footprint "eagle-import:NORDIC_NRF_2_RESC0402_L")
      (libsource (lib "eagle-import") (part "NORDIC_NRF_2_INDUCTOR_0402_L"))
    )
    (comp (ref "U$20")
      (value "4.7u")
      (footprint "eagle-import:NORDIC_NRF_3_RESC0201_L")
      (libsource (lib "eagle-import") (part "NORDIC_NRF_3_CAPACITOR_0201_L"))
    )
    (comp (ref "U$22")
      (value "32MHz")
      (footprint "eagle-import:NORDIC_NRF_BT-XTAL_2016_N")
      (libsource (lib "eagle-import") (part "NORDIC_NRF_XTAL_32MHZ"))
    )
    (comp (ref "U$31")
      (value "NORDIC_NRF_4_NRF52840_QF")
      (footprint "eagle-import:NORDIC_NRF_4_AQFN50P700X700X85_HS-74N")
      (libsource (lib "eagle-import") (part "NORDIC_NRF_4_NRF52840_QF"))
    )
    (comp (ref "U1")
      (value "ESP32_C6_LIBRARY_MAX17048G+T10")
      (footprint "eagle-import:ESP32_C6_LIBRARY_SON50P200X200X80-9N")
      (fields (field (name "MF") "Analog Devices") (field (name "MP") "MAX17048G+T10"))
      (libsource (lib "eagle-import") (part "ESP32_C6_LIBRARY_MAX17048G+T10"))
    )
    (comp (ref "X1")
      (value "32.768kHz")
      (footprint "eagle-import:NORDIC_NRF_1_XTAL_3215_N")
      (libsource (lib "eagle-import") (part "NORDIC_NRF_1_XTAL_32KHZ"))
    )
  )
  (nets
    (net (code "1") (name "/DEC1") (class "Default")
      (node (ref "C30") (pin "1") (pinfunction "1_1") (pintype "passive"))
      (node (ref "U$31") (pin "P$C1") (pinfunction "DEC1_P$C1") (pintype "power_in"))
    )
    (net (code "2") (name "/DEC3") (class "Default")
      (node (ref "C23") (pin "1") (pinfunction "1_1") (pintype "passive"))
      (node (ref "U$31") (pin "P$D23") (pinfunction "DEC3_P$D23") (pintype "bidirectional"))
    )
    (net (code "3") (name "/DEC4_6") (class "Default")
      (node (ref "C14") (pin "1") (pinfunction "1_1") (pintype "passive"))
      (node (ref "C20") (pin "1") (pinfunction "1_1") (pintype "passive"))
      (node (ref "C24") (pin "1") (pinfunction "1_1") (pintype "passive"))
      (node (ref "U$31") (pin "P$B5") (pinfunction "DEC4_P$B5") (pintype "power_in"))
      (node (ref "U$31") (pin "P$E24") (pinfunction "DEC6_P$E24") (pintype "bidirectional"))
      (node (ref "U$4") (pin "2") (pinfunction "2_2") (pintype "passive"))
    )
    (net (code "4") (name "/EP") (class "Default")
      (node (ref "U1") (pin "9") (pinfunction "EP_9") (pintype "power_in"))
    )
    (net (code "5") (name "3V3") (class "Default")
      (node (ref "C12") (pin "1") (pinfunction "1_1") (pintype "passive"))
      (node (ref "C13") (pin "1") (pinfunction "1_1") (pintype "passive"))
      (node (ref "C15") (pin "1") (pinfunction "1_1") (pintype "passive"))
      (node (ref "C22") (pin "1") (pinfunction "1_1") (pintype "passive"))
      (node (ref "C26") (pin "1") (pinfunction "1_1") (pintype "passive"))
      (node (ref "C3") (pin "1") (pinfunction "1_1") (pintype "passive"))
      (node (ref "C33") (pin "1") (pinfunction "1_1") (pintype "passive"))
      (node (ref "C36") (pin "1") (pinfunction "1_1") (pintype "passive"))
      (node (ref "C5") (pin "2") (pinfunction "2_2") (pintype "passive"))
      (node (ref "IC2") (pin "E2") (pinfunction "VOUT_1_E2") (pintype "bidirectional"))
      (node (ref "IC2") (pin "E3") (pinfunction "VOUT_2_E3") (pintype "bidirectional"))
      (node (ref "IC3") (pin "C2") (pinfunction "VDD_C2") (pintype "bidirectional"))
      (node (ref "IC4") (pin "10") (pinfunction "CSB_10") (pintype "bidirectional"))
      (node (ref "IC4") (pin "3") (pinfunction "VDDIO_3") (pintype "bidirectional"))
      (node (ref "IC4") (pin "7") (pinfunction "VDD_7") (pintype "bidirectional"))
      (node (ref "J2") (pin "1") (pinfunction "1_1") (pintype "bidirectional"))
      (node (ref "Q2") (pin "2") (pinfunction "S_2") (pintype "bidirectional"))
      (node (ref "R10") (pin "1") (pinfunction "1_1") (pintype "bidirectional"))
      (node (ref "R11") (pin "1") (pinfunction "1_1") (pintype "bidirectional"))
      (node (ref "R12") (pin "2") (pinfunction "2_2") (pintype "bidirectional"))
      (node (ref "R13") (pin "2") (pinfunction "2_2") (pintype "bidirectional"))
      (node (ref "R14") (pin "2") (pinfunction "2_2") (pintype "bidirectional"))
      (node (ref "R3") (pin "1") (pinfunction "1_1") (pintype "bidirectional"))
      (node (ref "TP7") (pin "TP") (pinfunction "TP_TP") (pintype "input"))
      (node (ref "U$31") (pin "P$A22") (pinfunction "VDD_P$A22") (pintype "power_in"))
      (node (ref "U$31") (pin "P$AD14") (pinfunction "VDD_P$AD14") (pintype "power_in"))
      (node (ref "U$31") (pin "P$AD23") (pinfunction "VDD_P$AD23") (pintype "power_in"))
      (node (ref "U$31") (pin "P$B1") (pinfunction "VDD_P$B1") (pintype "power_in"))
      (node (ref "U$31") (pin "P$W1") (pinfunction "VDD_P$W1") (pintype "power_in"))
      (node (ref "U$31") (pin "P$Y2") (pinfunction "VDDH_P$Y2") (pintype "power_in"))
    )
    (net (code "6") (name "ALERT") (class "Default")
      (node (ref "U$31") (pin "P$J24") (pinfunction "P0.10/NFC2_P$J24") (pintype "bidirectional"))
      (node (ref "U1") (pin "5") (pinfunction "~{ALERT}_5") (pintype "output"))
    )
    (net (code "7") (name "ANT") (class "Default")
      (node (ref "C29") (pin "1") (pinfunction "1_1") (pintype "passive"))
      (node (ref "U$31") (pin "P$H23") (pinfunction "ANT_P$H23") (pintype "bidirectional"))
      (node (ref "U$5") (pin "1") (pinfunction "1_1") (pintype "passive"))
    )
    (net (code "8") (name "DN") (class "Default")
      (node (ref "D4") (pin "1") (pinfunction "I/O1_1_1") (pintype "bidirectional"))
      (node (ref "J1") (pin "A7") (pinfunction "DN1_A7") (pintype "bidirectional"))
      (node (ref "J1") (pin "B7") (pinfunction "DN2_B7") (pintype "bidirectional"))
    )
    (net (code "9") (name "DP") (class "Default")
      (node (ref "D4") (pin "3") (pinfunction "I/O2_1_3") (pintype "bidirectional"))
      (node (ref "J1") (pin "A6") (pinfunction "DP1_A6") (pintype "bidirectional"))
      (node (ref "J1") (pin "B6") (pinfunction "DP2_B6") (pintype "bidirectional"))
    )
    (net (code "10") (name "D_N") (class "Default")
      (node (ref "D4") (pin "6") (pinfunction "I/O1_2_6") (pintype "bidirectional"))
      (node (ref "U$31") (pin "P$AD4") (pinfunction "D-_P$AD4") (pintype "bidirectional"))
    )
    (net (code "11") (name "D_P") (class "Default")
      (node (ref "D4") (pin "4") (pinfunction "I/O2_2_4") (pintype "bidirectional"))
      (node (ref "U$31") (pin "P$AD6") (pinfunction "D+_P$AD6") (pintype "bidirectional"))
    )
    (net (code "12") (name "EPD_3V3") (class "Default")
      (node (ref "C17") (pin "1") (pinfunction "1_1") (pintype "passive"))
      (node (ref "C48") (pin "2") (pinfunction "2_2") (pintype "passive"))
      (node (ref "J3") (pin "15") (pinfunction "15_15") (pintype "bidirectional"))
      (node (ref "J3") (pin "16") (pinfunction "16_16") (pintype "bidirectional"))
      (node (ref "L4") (pin "2") (pinfunction "2_2") (pintype "passive"))
      (node (ref "Q2") (pin "3") (pinfunction "D_3") (pintype "bidirectional"))
    )
    (net (code "13") (name "EPD_BUSY") (class "Default")
      (node (ref "J3") (pin "9") (pinfunction "9_9") (pintype "bidirectional"))
      (node (ref "U$31") (pin "P$AD12") (pinfunction "P0.17_P$AD12") (pintype "bidirectional"))
    )
    (net (code "14") (name "EPD_CS") (class "Default")
      (node (ref "J3") (pin "12") (pinfunction "12_12") (pintype "bidirectional"))
      (node (ref "U$31") (pin "P$K2") (pinfunction "P0.05/AIN3_P$K2") (pintype "bidirectional"))
    )
    (net (code "15") (name "EPD_DC") (class "Default")
      (node (ref "J3") (pin "11") (pinfunction "11_11") (pintype "bidirectional"))
      (node (ref "U$31") (pin "P$AD10") (pinfunction "P0.15_P$AD10") (pintype "bidirectional"))
    )
    (net (code "16") (name "EPD_RST") (class "Default")
      (node (ref "J3") (pin "10") (pinfunction "10_10") (pintype "bidirectional"))
      (node (ref "U$31") (pin "P$AC11") (pinfunction "P0.16_P$AC11") (pintype "bidirectional"))
    )
    (net (code "17") (name "GDR") (class "Default")
      (node (ref "J3") (pin "2") (pinfunction "2_2") (pintype "bidirectional"))
      (node (ref "Q1") (pin "1") (pinfunction "G_1") (pintype "bidirectional"))
      (node (ref "R1") (pin "1") (pinfunction "1_1") (pintype "bidirectional"))
    )
    (net (code "18") (name "HAPTIC_EN") (class "Default")
      (node (ref "IC3") (pin "A1") (pinfunction "EN_A1") (pintype "bidirectional"))
      (node (ref "U$31") (pin "P$U1") (pinfunction "P0.12_P$U1") (pintype "bidirectional"))
    )
    (net (code "19") (name "IMU_INT1") (class "Default")
      (node (ref "IC4") (pin "5") (pinfunction "INT1_5") (pintype "bidirectional"))
      (node (ref "U$31") (pin "P$N1") (pinfunction "P0.08_P$N1") (pintype "bidirectional"))
    )
    (net (code "20") (name "IMU_INT2") (class "Default")
      (node (ref "IC4") (pin "6") (pinfunction "INT2_6") (pintype "bidirectional"))
      (node (ref "U$31") (pin "P$P2") (pinfunction "P1.08_P$P2") (pintype "bidirectional"))
    )
    (net (code "21") (name "LX1") (class "Default")
      (node (ref "IC2") (pin "B2") (pinfunction "SW1_1_B2") (pintype "bidirectional"))
      (node (ref "IC2") (pin "B3") (pinfunction "SW1_2_B3") (pintype "bidirectional"))
      (node (ref "L2") (pin "1") (pinfunction "1_1") (pintype "bidirectional"))
    )
    (net (code "22") (name "LX2") (class "Default")
      (node (ref "IC2") (pin "D2") (pinfunction "SW2_1_D2") (pintype "bidirectional"))
      (node (ref "IC2") (pin "D3") (pinfunction "SW2_2_D3") (pintype "bidirectional"))
      (node (ref "L2") (pin "2") (pinfunction "2_2") (pintype "bidirectional"))
    )
    (net (code "23") (name "MOSI") (class "Default")
      (node (ref "J3") (pin "14") (pinfunction "14_14") (pintype "bidirectional"))
      (node (ref "U$31") (pin "P$B13") (pinfunction "P0.03/AIN1_P$B13") (pintype "bidirectional"))
    )
    (net (code "24") (name "Net-(ANT1-FEED)") (class "Default")
      (node (ref "ANT1") (pin "1") (pinfunction "FEED_1") (pintype "input"))
      (node (ref "C31") (pin "1") (pinfunction "1_1") (pintype "passive"))
      (node (ref "C32") (pin "1") (pinfunction "1_1") (pintype "passive"))
      (node (ref "U$5") (pin "2") (pinfunction "2_2") (pintype "passive"))
    )
    (net (code "25") (name "Net-(C38-Pad2)") (class "Default")
      (node (ref "C38") (pin "2") (pinfunction "2_2") (pintype "passive"))
      (node (ref "J3") (pin "4") (pinfunction "4_4") (pintype "bidirectional"))
    )
    (net (code "26") (name "Net-(C39-Pad2)") (class "Default")
      (node (ref "C39") (pin "2") (pinfunction "2_2") (pintype "passive"))
      (node (ref "J3") (pin "5") (pinfunction "5_5") (pintype "bidirectional"))
    )
    (net (code "27") (name "Net-(C40-Pad2)") (class "Default")
      (node (ref "C40") (pin "2") (pinfunction "2_2") (pintype "passive"))
      (node (ref "J3") (pin "17") (pinfunction "17_17") (pintype "bidirectional"))
    )
    (net (code "28") (name "Net-(C41-Pad2)") (class "Default")
      (node (ref "C41") (pin "2") (pinfunction "2_2") (pintype "passive"))
      (node (ref "J3") (pin "18") (pinfunction "18_18") (pintype "bidirectional"))
    )
    (net (code "29") (name "Net-(C42-Pad2)") (class "Default")
      (node (ref "C42") (pin "2") (pinfunction "2_2") (pintype "passive"))
      (node (ref "J3") (pin "19") (pinfunction "19_19") (pintype "bidirectional"))
    )
    (net (code "30") (name "Net-(C43-Pad2)") (class "Default")
      (node (ref "C43") (pin "2") (pinfunction "2_2") (pintype "passive"))
      (node (ref "J3") (pin "20") (pinfunction "20_20") (pintype "bidirectional"))
    )
    (net (code "31") (name "Net-(C45-Pad2)") (class "Default")
      (node (ref "C45") (pin "2") (pinfunction "2_2") (pintype "passive"))
      (node (ref "J3") (pin "22") (pinfunction "22_22") (pintype "bidirectional"))
    )
    (net (code "32") (name "Net-(C47-Pad2)") (class "Default")
      (node (ref "C47") (pin "2") (pinfunction "2_2") (pintype "passive"))
      (node (ref "J3") (pin "24") (pinfunction "24_24") (pintype "bidirectional"))
    )
    (net (code "33") (name "Net-(D1-A)") (class "Default")
      (node (ref "C16") (pin "1") (pinfunction "1_1") (pintype "passive"))
      (node (ref "D1") (pin "2") (pinfunction "A_2") (pintype "bidirectional"))
      (node (ref "D2") (pin "1") (pinfunction "K_1") (pintype "bidirectional"))
    )
    (net (code "34") (name "Net-(D3-A)") (class "Default")
      (node (ref "C16") (pin "2") (pinfunction "2_2") (pintype "passive"))
      (node (ref "D3") (pin "2") (pinfunction "A_2") (pintype "bidirectional"))
      (node (ref "L4") (pin "1") (pinfunction "1_1") (pintype "passive"))
      (node (ref "Q1") (pin "3") (pinfunction "D_3") (pintype "bidirectional"))
    )
    (net (code "35") (name "Net-(IC1-TS{slash}MR)") (class "Default")
      (node (ref "IC1") (pin "D1") (pinfunction "TS/MR_D1") (pintype "bidirectional"))
      (node (ref "R5") (pin "2") (pinfunction "2_2") (pintype "bidirectional"))
    )
    (net (code "36") (name "Net-(IC2-SCL)") (class "Default")
      (node (ref "IC2") (pin "D1") (pinfunction "SCL_D1") (pintype "bidirectional"))
      (node (ref "R6") (pin "1") (pinfunction "1_1") (pintype "bidirectional"))
    )
    (net (code "37") (name "Net-(IC2-SDA)") (class "Default")
      (node (ref "IC2") (pin "E1") (pinfunction "SDA_E1") (pintype "bidirectional"))
      (node (ref "R7") (pin "1") (pinfunction "1_1") (pintype "bidirectional"))
    )
    (net (code "38") (name "Net-(IC3-REG)") (class "Default")
      (node (ref "C6") (pin "2") (pinfunction "2_2") (pintype "passive"))
      (node (ref "IC3") (pin "A2") (pinfunction "REG_A2") (pintype "bidirectional"))
    )
    (net (code "39") (name "Net-(IC4-SDO)") (class "Default")
      (node (ref "IC4") (pin "1") (pinfunction "SDO_1") (pintype "bidirectional"))
      (node (ref "R15") (pin "1") (pinfunction "1_1") (pintype "bidirectional"))
    )
    (net (code "40") (name "Net-(J1-CC1)") (class "Default")
      (node (ref "J1") (pin "A5") (pinfunction "CC1_A5") (pintype "bidirectional"))
      (node (ref "R8") (pin "2") (pinfunction "2_2") (pintype "bidirectional"))
    )
    (net (code "41") (name "Net-(J1-CC2)") (class "Default")
      (node (ref "J1") (pin "B5") (pinfunction "CC2_B5") (pintype "bidirectional"))
      (node (ref "R9") (pin "1") (pinfunction "1_1") (pintype "bidirectional"))
    )
    (net (code "42") (name "Net-(Q1-S)") (class "Default")
      (node (ref "Q1") (pin "2") (pinfunction "S_2") (pintype "bidirectional"))
      (node (ref "R2") (pin "1") (pinfunction "1_1") (pintype "bidirectional"))
    )
    (net (code "43") (name "Net-(R2-Pad2)") (class "Default")
      (node (ref "R2") (pin "2") (pinfunction "2_2") (pintype "bidirectional"))
      (node (ref "R4") (pin "1") (pinfunction "1_1") (pintype "bidirectional"))
      (node (ref "SJ1") (pin "1") (pinfunction "1_1") (pintype "passive"))
    )
    (net (code "44") (name "Net-(U$4-Pad1)") (class "Default")
      (node (ref "U$4") (pin "1") (pinfunction "1_1") (pintype "passive"))
      (node (ref "U$8") (pin "2") (pinfunction "2_2") (pintype "passive"))
    )
    (net (code "45") (name "Net-(U$31-DCC)") (class "Default")
      (node (ref "U$31") (pin "P$B3") (pinfunction "DCC_P$B3") (pintype "output"))
      (node (ref "U$8") (pin "1") (pinfunction "1_1") (pintype "passive"))
    )
    (net (code "46") (name "Net-(U$31-DEC2)") (class "Default")
      (node (ref "C21") (pin "1") (pinfunction "1_1") (pintype "passive"))
      (node (ref "U$31") (pin "P$A18") (pinfunction "DEC2_P$A18") (pintype "bidirectional"))
    )
    (net (code "47") (name "Net-(U$31-DEC3V3)") (class "Default")
      (node (ref "C35") (pin "1") (pinfunction "1_1") (pintype "passive"))
      (node (ref "U$31") (pin "P$AC5") (pinfunction "DEC3V3_P$AC5") (pintype "bidirectional"))
    )
    (net (code "48") (name "Net-(U$31-DEC5)") (class "Default")
      (node (ref "C25") (pin "1") (pinfunction "1_1") (pintype "passive"))
      (node (ref "U$31") (pin "P$N24") (pinfunction "DEC5_P$N24") (pintype "bidirectional"))
    )
    (net (code "49") (name "Net-(U$31-P0.00{slash}XL1)") (class "Default")
      (node (ref "C18") (pin "2") (pinfunction "2_2") (pintype "passive"))
      (node (ref "U$31") (pin "P$D2") (pinfunction "P0.00/XL1_P$D2") (pintype "bidirectional"))
      (node (ref "X1") (pin "2") (pinfunction "2_2") (pintype "passive"))
    )
    (net (code "50") (name "Net-(U$31-P0.01{slash}XL2)") (class "Default")
      (node (ref "C19") (pin "2") (pinfunction "2_2") (pintype "passive"))
      (node (ref "U$31") (pin "P$F2") (pinfunction "P0.01/XL2_P$F2") (pintype "bidirectional"))
      (node (ref "X1") (pin "1") (pinfunction "1_1") (pintype "passive"))
    )
    (net (code "51") (name "OUT+") (class "Default")
      (node (ref "IC3") (pin "A3") (pinfunction "OUT+_A3") (pintype "bidirectional"))
      (node (ref "TP10") (pin "TP") (pinfunction "TP_TP") (pintype "input"))
    )
    (net (code "52") (name "OUT-") (class "Default")
      (node (ref "IC3") (pin "C3") (pinfunction "OUT-_C3") (pintype "bidirectional"))
      (node (ref "TP11") (pin "TP") (pinfunction "TP_TP") (pintype "input"))
    )
    (net (code "53") (name "P0.04") (class "Default")
      (node (ref "U$31") (pin "P$J1") (pinfunction "P0.04/AIN2_P$J1") (pintype "bidirectional"))
    )
    (net (code "54") (name "P0.09") (class "Default")
      (node (ref "U$31") (pin "P$L24") (pinfunction "P0.09/NFC1_P$L24") (pintype "bidirectional"))
    )
    (net (code "55") (name "P0.13") (class "Default")
      (node (ref "C7") (pin "2") (pinfunction "2_2") (pintype "passive"))
      (node (ref "R12") (pin "1") (pinfunction "1_1") (pintype "bidirectional"))
      (node (ref "SW1") (pin "2") (pinfunction "2_2") (pintype "passive"))
      (node (ref "U$31") (pin "P$AD8") (pinfunction "P0.13_P$AD8") (pintype "bidirectional"))
    )
    (net (code "56") (name "P0.14") (class "Default")
      (node (ref "C8") (pin "2") (pinfunction "2_2") (pintype "passive"))
      (node (ref "R13") (pin "1") (pinfunction "1_1") (pintype "bidirectional"))
      (node (ref "SW2") (pin "2") (pinfunction "2_2") (pintype "passive"))
      (node (ref "U$31") (pin "P$AC9") (pinfunction "P0.14_P$AC9") (pintype "bidirectional"))
    )
    (net (code "57") (name "P0.19") (class "Default")
      (node (ref "U$31") (pin "P$AC15") (pinfunction "P0.19_P$AC15") (pintype "bidirectional"))
    )
    (net (code "58") (name "P0.20") (class "Default")
      (node (ref "U$31") (pin "P$AD16") (pinfunction "P0.20_P$AD16") (pintype "bidirectional"))
    )
    (net (code "59") (name "P0.21") (class "Default")
      (node (ref "U$31") (pin "P$AC17") (pinfunction "P0.21_P$AC17") (pintype "bidirectional"))
    )
    (net (code "60") (name "P0.22") (class "Default")
      (node (ref "U$31") (pin "P$AD18") (pinfunction "P0.22_P$AD18") (pintype "bidirectional"))
    )
    (net (code "61") (name "P0.23") (class "Default")
      (node (ref "U$31") (pin "P$AC19") (pinfunction "P0.23_P$AC19") (pintype "bidirectional"))
    )
    (net (code "62") (name "P0.24") (class "Default")
      (node (ref "U$31") (pin "P$AD20") (pinfunction "P0.24_P$AD20") (pintype "bidirectional"))
    )
    (net (code "63") (name "P0.25") (class "Default")
      (node (ref "U$31") (pin "P$AC21") (pinfunction "P0.25_P$AC21") (pintype "bidirectional"))
    )
    (net (code "64") (name "P0.26") (class "Default")
      (node (ref "U$31") (pin "P$G1") (pinfunction "P0.26_P$G1") (pintype "bidirectional"))
    )
    (net (code "65") (name "P0.27") (class "Default")
      (node (ref "U$31") (pin "P$H2") (pinfunction "P0.27_P$H2") (pintype "bidirectional"))
    )
    (net (code "66") (name "P0.28") (class "Default")
      (node (ref "U$31") (pin "P$B11") (pinfunction "P0.28/AIN4_P$B11") (pintype "bidirectional"))
    )
    (net (code "67") (name "P0.29") (class "Default")
      (node (ref "U$31") (pin "P$A10") (pinfunction "P0.29/AIN5_P$A10") (pintype "bidirectional"))
    )
    (net (code "68") (name "P0.30") (class "Default")
      (node (ref "U$31") (pin "P$B9") (pinfunction "P0.30/AIN6_P$B9") (pintype "bidirectional"))
    )
    (net (code "69") (name "P0.31") (class "Default")
      (node (ref "U$31") (pin "P$A8") (pinfunction "P0.31/AIN7_P$A8") (pintype "bidirectional"))
    )
    (net (code "70") (name "P1.01") (class "Default")
      (node (ref "Q2") (pin "1") (pinfunction "G_1") (pintype "bidirectional"))
      (node (ref "R3") (pin "2") (pinfunction "2_2") (pintype "bidirectional"))
      (node (ref "U$31") (pin "P$Y23") (pinfunction "P1.01_P$Y23") (pintype "bidirectional"))
    )
    (net (code "71") (name "P1.02") (class "Default")
      (node (ref "C9") (pin "2") (pinfunction "2_2") (pintype "passive"))
      (node (ref "R14") (pin "1") (pinfunction "1_1") (pintype "bidirectional"))
      (node (ref "SW3") (pin "2") (pinfunction "2_2") (pintype "passive"))
      (node (ref "U$31") (pin "P$W24") (pinfunction "P1.02_P$W24") (pintype "bidirectional"))
    )
    (net (code "72") (name "P1.03") (class "Default")
      (node (ref "U$31") (pin "P$V23") (pinfunction "P1.03_P$V23") (pintype "bidirectional"))
    )
    (net (code "73") (name "P1.04") (class "Default")
      (node (ref "U$31") (pin "P$U24") (pinfunction "P1.04_P$U24") (pintype "bidirectional"))
    )
    (net (code "74") (name "P1.05") (class "Default")
      (node (ref "U$31") (pin "P$T23") (pinfunction "P1.05_P$T23") (pintype "bidirectional"))
    )
    (net (code "75") (name "P1.06") (class "Default")
      (node (ref "U$31") (pin "P$R24") (pinfunction "P1.06_P$R24") (pintype "bidirectional"))
    )
    (net (code "76") (name "P1.07") (class "Default")
      (node (ref "U$31") (pin "P$P23") (pinfunction "P1.07_P$P23") (pintype "bidirectional"))
    )
    (net (code "77") (name "P1.09") (class "Default")
      (node (ref "U$31") (pin "P$R1") (pinfunction "P1.09_P$R1") (pintype "bidirectional"))
    )
    (net (code "78") (name "P1.10") (class "Default")
      (node (ref "U$31") (pin "P$A20") (pinfunction "P1.10_P$A20") (pintype "bidirectional"))
    )
    (net (code "79") (name "P1.11") (class "Default")
      (node (ref "U$31") (pin "P$B19") (pinfunction "P1.11_P$B19") (pintype "bidirectional"))
    )
    (net (code "80") (name "P1.12") (class "Default")
      (node (ref "U$31") (pin "P$B17") (pinfunction "P1.12_P$B17") (pintype "bidirectional"))
    )
    (net (code "81") (name "P1.13") (class "Default")
      (node (ref "U$31") (pin "P$A16") (pinfunction "P1.13_P$A16") (pintype "bidirectional"))
    )
    (net (code "82") (name "P1.14") (class "Default")
      (node (ref "U$31") (pin "P$B15") (pinfunction "P1.14_P$B15") (pintype "bidirectional"))
    )
    (net (code "83") (name "P1.15") (class "Default")
      (node (ref "U$31") (pin "P$A14") (pinfunction "P1.15_P$A14") (pintype "bidirectional"))
    )
    (net (code "84") (name "PMIC_INT") (class "Default")
      (node (ref "IC1") (pin "A1") (pinfunction "~{INT}_A1") (pintype "bidirectional"))
      (node (ref "U$31") (pin "P$T2") (pinfunction "P0.11_P$T2") (pintype "bidirectional"))
    )
    (net (code "85") (name "PREVGH") (class "Default")
      (node (ref "C44") (pin "2") (pinfunction "2_2") (pintype "passive"))
      (node (ref "D3") (pin "1") (pinfunction "K_1") (pintype "bidirectional"))
      (node (ref "J3") (pin "21") (pinfunction "21_21") (pintype "bidirectional"))
    )
    (net (code "86") (name "PREVGL") (class "Default")
      (node (ref "C46") (pin "2") (pinfunction "2_2") (pintype "passive"))
      (node (ref "D2") (pin "2") (pinfunction "A_2") (pintype "bidirectional"))
      (node (ref "J3") (pin "23") (pinfunction "23_23") (pintype "bidirectional"))
    )
    (net (code "87") (name "RESE") (class "Default")
      (node (ref "J3") (pin "3") (pinfunction "3_3") (pintype "bidirectional"))
    )
    (net (code "88") (name "RESET") (class "Default")
      (node (ref "TP4") (pin "TP") (pinfunction "TP_TP") (pintype "input"))
      (node (ref "U$31") (pin "P$AC13") (pinfunction "P0.18/RESET_P$AC13") (pintype "bidirectional"))
    )
    (net (code "89") (name "SCK") (class "Default")
      (node (ref "J3") (pin "13") (pinfunction "13_13") (pintype "bidirectional"))
      (node (ref "U$31") (pin "P$A12") (pinfunction "P0.02/AIN0_P$A12") (pintype "bidirectional"))
    )
    (net (code "90") (name "SCL") (class "Default")
      (node (ref "IC1") (pin "B1") (pinfunction "SCL_B1") (pintype "bidirectional"))
      (node (ref "IC3") (pin "C1") (pinfunction "SCL_C1") (pintype "bidirectional"))
      (node (ref "IC4") (pin "12") (pinfunction "SCX_12") (pintype "bidirectional"))
      (node (ref "R10") (pin "2") (pinfunction "2_2") (pintype "bidirectional"))
      (node (ref "R6") (pin "2") (pinfunction "2_2") (pintype "bidirectional"))
      (node (ref "TP6") (pin "TP") (pinfunction "TP_TP") (pintype "input"))
      (node (ref "U$31") (pin "P$M2") (pinfunction "P0.07_P$M2") (pintype "bidirectional"))
      (node (ref "U1") (pin "7") (pinfunction "SCL_7") (pintype "input"))
    )
    (net (code "91") (name "SDA") (class "Default")
      (node (ref "IC1") (pin "C1") (pinfunction "SDA_C1") (pintype "bidirectional"))
      (node (ref "IC3") (pin "B2") (pinfunction "SDA_B2") (pintype "bidirectional"))
      (node (ref "IC4") (pin "2") (pinfunction "SDX_2") (pintype "bidirectional"))
      (node (ref "R11") (pin "2") (pinfunction "2_2") (pintype "bidirectional"))
      (node (ref "R7") (pin "2") (pinfunction "2_2") (pintype "bidirectional"))
      (node (ref "TP8") (pin "TP") (pinfunction "TP_TP") (pintype "input"))
      (node (ref "U$31") (pin "P$L1") (pinfunction "P0.06_P$L1") (pintype "bidirectional"))
      (node (ref "U1") (pin "8") (pinfunction "SDA_8") (pintype "bidirectional"))
    )
    (net (code "92") (name "SPARKFUN-POWERSYMBOLS_GND") (class "Default")
      (node (ref "C1") (pin "1") (pinfunction "1_1") (pintype "passive"))
      (node (ref "C10") (pin "1") (pinfunction "1_1") (pintype "passive"))
      (node (ref "C11") (pin "2") (pinfunction "2_2") (pintype "passive"))
      (node (ref "C12") (pin "2") (pinfunction "2_2") (pintype "passive"))
      (node (ref "C13") (pin "2") (pinfunction "2_2") (pintype "passive"))
      (node (ref "C14") (pin "2") (pinfunction "2_2") (pintype "passive"))
      (node (ref "C15") (pin "2") (pinfunction "2_2") (pintype "passive"))
      (node (ref "C17") (pin "2") (pinfunction "2_2") (pintype "passive"))
      (node (ref "C18") (pin "1") (pinfunction "1_1") (pintype "passive"))
      (node (ref "C19") (pin "1") (pinfunction "1_1") (pintype "passive"))
      (node (ref "C2") (pin "1") (pinfunction "1_1") (pintype "passive"))
      (node (ref "C20") (pin "2") (pinfunction "2_2") (pintype "passive"))
      (node (ref "C21") (pin "2") (pinfunction "2_2") (pintype "passive"))
      (node (ref "C22") (pin "2") (pinfunction "2_2") (pintype "passive"))
      (node (ref "C23") (pin "2") (pinfunction "2_2") (pintype "passive"))
      (node (ref "C24") (pin "2") (pinfunction "2_2") (pintype "passive"))
      (node (ref "C25") (pin "2") (pinfunction "2_2") (pintype "passive"))
      (node (ref "C26") (pin "2") (pinfunction "2_2") (pintype "passive"))
      (node (ref "C27") (pin "2") (pinfunction "2_2") (pintype "passive"))
      (node (ref "C28") (pin "2") (pinfunction "2_2") (pintype "passive"))
      (node (ref "C29") (pin "2") (pinfunction "2_2") (pintype "passive"))
      (node (ref "C3") (pin "2") (pinfunction "2_2") (pintype "passive"))
      (node (ref "C30") (pin "2") (pinfunction "2_2") (pintype "passive"))
      (node (ref "C31") (pin "2") (pinfunction "2_2") (pintype "passive"))
      (node (ref "C32") (pin "2") (pinfunction "2_2") (pintype "passive"))
      (node (ref "C33") (pin "2") (pinfunction "2_2") (pintype "passive"))
      (node (ref "C34") (pin "2") (pinfunction "2_2") (pintype "passive"))
      (node (ref "C35") (pin "2") (pinfunction "2_2") (pintype "passive"))
      (node (ref "C36") (pin "2") (pinfunction "2_2") (pintype "passive"))
      (node (ref "C37") (pin "1") (pinfunction "1_1") (pintype "passive"))
      (node (ref "C38") (pin "1") (pinfunction "1_1") (pintype "passive"))
      (node (ref "C39") (pin "1") (pinfunction "1_1") (pintype "passive"))
      (node (ref "C4") (pin "1") (pinfunction "1_1") (pintype "passive"))
      (node (ref "C40") (pin "1") (pinfunction "1_1") (pintype "passive"))
      (node (ref "C41") (pin "1") (pinfunction "1_1") (pintype "passive"))
      (node (ref "C42") (pin "1") (pinfunction "1_1") (pintype "passive"))
      (node (ref "C43") (pin "1") (pinfunction "1_1") (pintype "passive"))
      (node (ref "C44") (pin "1") (pinfunction "1_1") (pintype "passive"))
      (node (ref "C45") (pin "1") (pinfunction "1_1") (pintype "passive"))
      (node (ref "C46") (pin "1") (pinfunction "1_1") (pintype "passive"))
      (node (ref "C47") (pin "1") (pinfunction "1_1") (pintype "passive"))
      (node (ref "C48") (pin "1") (pinfunction "1_1") (pintype "passive"))
      (node (ref "C49") (pin "2") (pinfunction "2_2") (pintype "passive"))
      (node (ref "C5") (pin "1") (pinfunction "1_1") (pintype "passive"))
      (node (ref "C6") (pin "1") (pinfunction "1_1") (pintype "passive"))
      (node (ref "C7") (pin "1") (pinfunction "1_1") (pintype "passive"))
      (node (ref "C8") (pin "1") (pinfunction "1_1") (pintype "passive"))
      (node (ref "C9") (pin "1") (pinfunction "1_1") (pintype "passive"))
      (node (ref "D1") (pin "1") (pinfunction "K_1") (pintype "bidirectional"))
      (node (ref "D4") (pin "2") (pinfunction "GND_2") (pintype "bidirectional"))
      (node (ref "IC1") (pin "D2") (pinfunction "GND_D2") (pintype "bidirectional"))
      (node (ref "IC2") (pin "B1") (pinfunction "VSEL_B1") (pintype "bidirectional"))
      (node (ref "IC2") (pin "C1") (pinfunction "AGND_C1") (pintype "bidirectional"))
      (node (ref "IC2") (pin "C2") (pinfunction "PGND_1_C2") (pintype "bidirectional"))
      (node (ref "IC2") (pin "C3") (pinfunction "PGND_2_C3") (pintype "bidirectional"))
      (node (ref "IC3") (pin "B1") (pinfunction "IN/TRIG_B1") (pintype "bidirectional"))
      (node (ref "IC3") (pin "B3") (pinfunction "GND_B3") (pintype "bidirectional"))
      (node (ref "IC4") (pin "8") (pinfunction "GNDIO_8") (pintype "bidirectional"))
      (node (ref "IC4") (pin "9") (pinfunction "GND_9") (pintype "bidirectional"))
      (node (ref "J1") (pin "A12_B1") (pinfunction "GND_A12_B1") (pintype "power_in"))
      (node (ref "J1") (pin "A1_B12") (pinfunction "GND_A1_B12") (pintype "power_in"))
      (node (ref "J1") (pin "SH1") (pinfunction "SHIELD_SH1") (pintype "passive"))
      (node (ref "J1") (pin "SH2") (pinfunction "SHIELD_SH2") (pintype "passive"))
      (node (ref "J1") (pin "SH3") (pinfunction "SHIELD_SH3") (pintype "passive"))
      (node (ref "J1") (pin "SH4") (pinfunction "SHIELD_SH4") (pintype "passive"))
      (node (ref "J2") (pin "3") (pinfunction "3_3") (pintype "bidirectional"))
      (node (ref "J2") (pin "5") (pinfunction "5_5") (pintype "bidirectional"))
      (node (ref "J3") (pin "8") (pinfunction "8_8") (pintype "bidirectional"))
      (node (ref "J3") (pin "MP1") (pinfunction "MP1_MP1") (pintype "bidirectional"))
      (node (ref "J3") (pin "MP2") (pinfunction "MP2_MP2") (pintype "bidirectional"))
      (node (ref "R1") (pin "2") (pinfunction "2_2") (pintype "bidirectional"))
      (node (ref "R15") (pin "2") (pinfunction "2_2") (pintype "bidirectional"))
      (node (ref "R4") (pin "2") (pinfunction "2_2") (pintype "bidirectional"))
      (node (ref "R5") (pin "1") (pinfunction "1_1") (pintype "bidirectional"))
      (node (ref "R8") (pin "1") (pinfunction "1_1") (pintype "bidirectional"))
      (node (ref "R9") (pin "2") (pinfunction "2_2") (pintype "bidirectional"))
      (node (ref "SJ1") (pin "2") (pinfunction "2_2") (pintype "passive"))
      (node (ref "SW1") (pin "1") (pinfunction "1_1") (pintype "passive"))
      (node (ref "SW2") (pin "1") (pinfunction "1_1") (pintype "passive"))
      (node (ref "SW3") (pin "1") (pinfunction "1_1") (pintype "passive"))
      (node (ref "TP13") (pin "TP") (pinfunction "TP_TP") (pintype "input"))
      (node (ref "TP5") (pin "TP") (pinfunction "TP_TP") (pintype "input"))
      (node (ref "U$20") (pin "2") (pinfunction "2_2") (pintype "passive"))
      (node (ref "U$22") (pin "2") (pinfunction "2_2") (pintype "passive"))
      (node (ref "U$22") (pin "4") (pinfunction "4_4") (pintype "passive"))
      (node (ref "U$31") (pin "P$74") (pinfunction "VSS_PAD_P$74") (pintype "bidirectional"))
      (node (ref "U$31") (pin "P$75") (pinfunction "VSS_PAD_P$75") (pintype "bidirectional"))
      (node (ref "U$31") (pin "P$76") (pinfunction "VSS_PAD_P$76") (pintype "bidirectional"))
      (node (ref "U$31") (pin "P$77") (pinfunction "VSS_PAD_P$77") (pintype "bidirectional"))
      (node (ref "U$31") (pin "P$78") (pinfunction "VSS_PAD_P$78") (pintype "bidirectional"))
      (node (ref "U$31") (pin "P$79") (pinfunction "VSS_PAD_P$79") (pintype "bidirectional"))
      (node (ref "U$31") (pin "P$80") (pinfunction "VSS_PAD_P$80") (pintype "bidirectional"))
      (node (ref "U$31") (pin "P$81") (pinfunction "VSS_PAD_P$81") (pintype "bidirectional"))
      (node (ref "U$31") (pin "P$82") (pinfunction "VSS_PAD_P$82") (pintype "bidirectional"))
      (node (ref "U$31") (pin "P$83") (pinfunction "VSS_PAD_P$83") (pintype "bidirectional"))
      (node (ref "U$31") (pin "P$84") (pinfunction "VSS_PAD_P$84") (pintype "bidirectional"))
      (node (ref "U$31") (pin "P$85") (pinfunction "VSS_PAD_P$85") (pintype "bidirectional"))
      (node (ref "U$31") (pin "P$86") (pinfunction "VSS_PAD_P$86") (pintype "bidirectional"))
      (node (ref "U$31") (pin "P$87") (pinfunction "VSS_PAD_P$87") (pintype "bidirectional"))
      (node (ref "U$31") (pin "P$88") (pinfunction "VSS_PAD_P$88") (pintype "bidirectional"))
      (node (ref "U$31") (pin "P$89") (pinfunction "VSS_PAD_P$89") (pintype "bidirectional"))
      (node (ref "U$31") (pin "P$90") (pinfunction "VSS_PAD_P$90") (pintype "bidirectional"))
      (node (ref "U$31") (pin "P$B7") (pinfunction "VSS_P$B7") (pintype "power_in"))
      (node (ref "U$31") (pin "P$F23") (pinfunction "VSS_PA_P$F23") (pintype "bidirectional"))
      (node (ref "U1") (pin "1") (pinfunction "CTG_1") (pintype "power_in"))
      (node (ref "U1") (pin "4") (pinfunction "GND_4") (pintype "power_in"))
      (node (ref "U1") (pin "6") (pinfunction "QSTRT_6") (pintype "input"))
    )
    (net (code "93") (name "SWDCLK") (class "Default")
      (node (ref "J2") (pin "4") (pinfunction "4_4") (pintype "bidirectional"))
      (node (ref "TP3") (pin "TP") (pinfunction "TP_TP") (pintype "input"))
      (node (ref "U$31") (pin "P$AA24") (pinfunction "SWDCLK_P$AA24") (pintype "input"))
    )
    (net (code "94") (name "SWDIO") (class "Default")
      (node (ref "J2") (pin "2") (pinfunction "2_2") (pintype "bidirectional"))
      (node (ref "TP2") (pin "TP") (pinfunction "TP_TP") (pintype "input"))
      (node (ref "U$31") (pin "P$AC24") (pinfunction "SWDIO_P$AC24") (pintype "bidirectional"))
    )
    (net (code "95") (name "SWO") (class "Default")
      (node (ref "J2") (pin "6") (pinfunction "6_6") (pintype "bidirectional"))
      (node (ref "TP1") (pin "TP") (pinfunction "TP_TP") (pintype "input"))
      (node (ref "U$31") (pin "P$AD22") (pinfunction "P1.00_P$AD22") (pintype "bidirectional"))
    )
    (net (code "96") (name "VBAT") (class "Default")
      (node (ref "C10") (pin "2") (pinfunction "2_2") (pintype "passive"))
      (node (ref "C2") (pin "2") (pinfunction "2_2") (pintype "passive"))
      (node (ref "IC1") (pin "C2") (pinfunction "BAT_C2") (pintype "bidirectional"))
      (node (ref "TP12") (pin "TP") (pinfunction "TP_TP") (pintype "input"))
      (node (ref "U1") (pin "2") (pinfunction "CELL_2") (pintype "power_in"))
      (node (ref "U1") (pin "3") (pinfunction "VDD_3") (pintype "power_in"))
    )
    (net (code "97") (name "VBUS") (class "Default")
      (node (ref "C1") (pin "2") (pinfunction "2_2") (pintype "passive"))
      (node (ref "C34") (pin "1") (pinfunction "1_1") (pintype "passive"))
      (node (ref "C4") (pin "2") (pinfunction "2_2") (pintype "passive"))
      (node (ref "D4") (pin "5") (pinfunction "VBUS_5") (pintype "bidirectional"))
      (node (ref "IC1") (pin "A2") (pinfunction "IN_A2") (pintype "bidirectional"))
      (node (ref "J1") (pin "A4_B9") (pinfunction "VBUS_A4_B9") (pintype "power_in"))
      (node (ref "J1") (pin "A9_B4") (pinfunction "VBUS_A9_B4") (pintype "power_in"))
      (node (ref "U$20") (pin "1") (pinfunction "1_1") (pintype "passive"))
      (node (ref "U$31") (pin "P$AD2") (pinfunction "VBUS_P$AD2") (pintype "power_in"))
    )
    (net (code "98") (name "VREG") (class "Default")
      (node (ref "C11") (pin "1") (pinfunction "1_1") (pintype "passive"))
      (node (ref "C37") (pin "2") (pinfunction "2_2") (pintype "passive"))
      (node (ref "C49") (pin "1") (pinfunction "1_1") (pintype "passive"))
      (node (ref "IC1") (pin "B2") (pinfunction "SYS_B2") (pintype "bidirectional"))
      (node (ref "IC2") (pin "A1") (pinfunction "EN_A1") (pintype "bidirectional"))
      (node (ref "IC2") (pin "A2") (pinfunction "VIN_1_A2") (pintype "bidirectional"))
      (node (ref "IC2") (pin "A3") (pinfunction "VIN_2_A3") (pintype "bidirectional"))
      (node (ref "TP9") (pin "TP") (pinfunction "TP_TP") (pintype "input"))
    )
    (net (code "99") (name "XC1") (class "Default")
      (node (ref "C28") (pin "1") (pinfunction "1_1") (pintype "passive"))
      (node (ref "U$22") (pin "1") (pinfunction "1_1") (pintype "passive"))
      (node (ref "U$31") (pin "P$B24") (pinfunction "XC1_P$B24") (pintype "input"))
    )
    (net (code "100") (name "XC2") (class "Default")
      (node (ref "C27") (pin "1") (pinfunction "1_1") (pintype "passive"))
      (node (ref "U$22") (pin "3") (pinfunction "3_3") (pintype "passive"))
      (node (ref "U$31") (pin "P$A23") (pinfunction "XC2_P$A23") (pintype "output"))
    )
    (net (code "101") (name "unconnected-(ANT1-NC-Pad2)") (class "Default")
      (node (ref "ANT1") (pin "2") (pinfunction "NC_2") (pintype "no_connect"))
    )
    (net (code "102") (name "unconnected-(IC4-ASCL-Pad11)") (class "Default")
      (node (ref "IC4") (pin "11") (pinfunction "ASCL_11") (pintype "bidirectional"))
    )
    (net (code "103") (name "unconnected-(IC4-ASDA-Pad4)") (class "Default")
      (node (ref "IC4") (pin "4") (pinfunction "ASDA_4") (pintype "bidirectional"))
    )
    (net (code "104") (name "unconnected-(J1-SBU1-PadA8)") (class "Default")
      (node (ref "J1") (pin "A8") (pinfunction "SBU1_A8") (pintype "bidirectional"))
    )
    (net (code "105") (name "unconnected-(J1-SBU2-PadB8)") (class "Default")
      (node (ref "J1") (pin "B8") (pinfunction "SBU2_B8") (pintype "bidirectional"))
    )
    (net (code "106") (name "unconnected-(J3-Pad1)") (class "Default")
      (node (ref "J3") (pin "1") (pinfunction "1_1") (pintype "bidirectional"))
    )
    (net (code "107") (name "unconnected-(J3-Pad6)") (class "Default")
      (node (ref "J3") (pin "6") (pinfunction "6_6") (pintype "bidirectional"))
    )
    (net (code "108") (name "unconnected-(J3-Pad7)") (class "Default")
      (node (ref "J3") (pin "7") (pinfunction "7_7") (pintype "bidirectional"))
    )
    (net (code "109") (name "unconnected-(U$31-DCCH-PadP$AB2)") (class "Default")
      (node (ref "U$31") (pin "P$AB2") (pinfunction "DCCH_P$AB2") (pintype "bidirectional"))
    )
  )
)
